# EasyEDA_schematics.net
KiCad netlist of a schematic drawn in EasyEDA
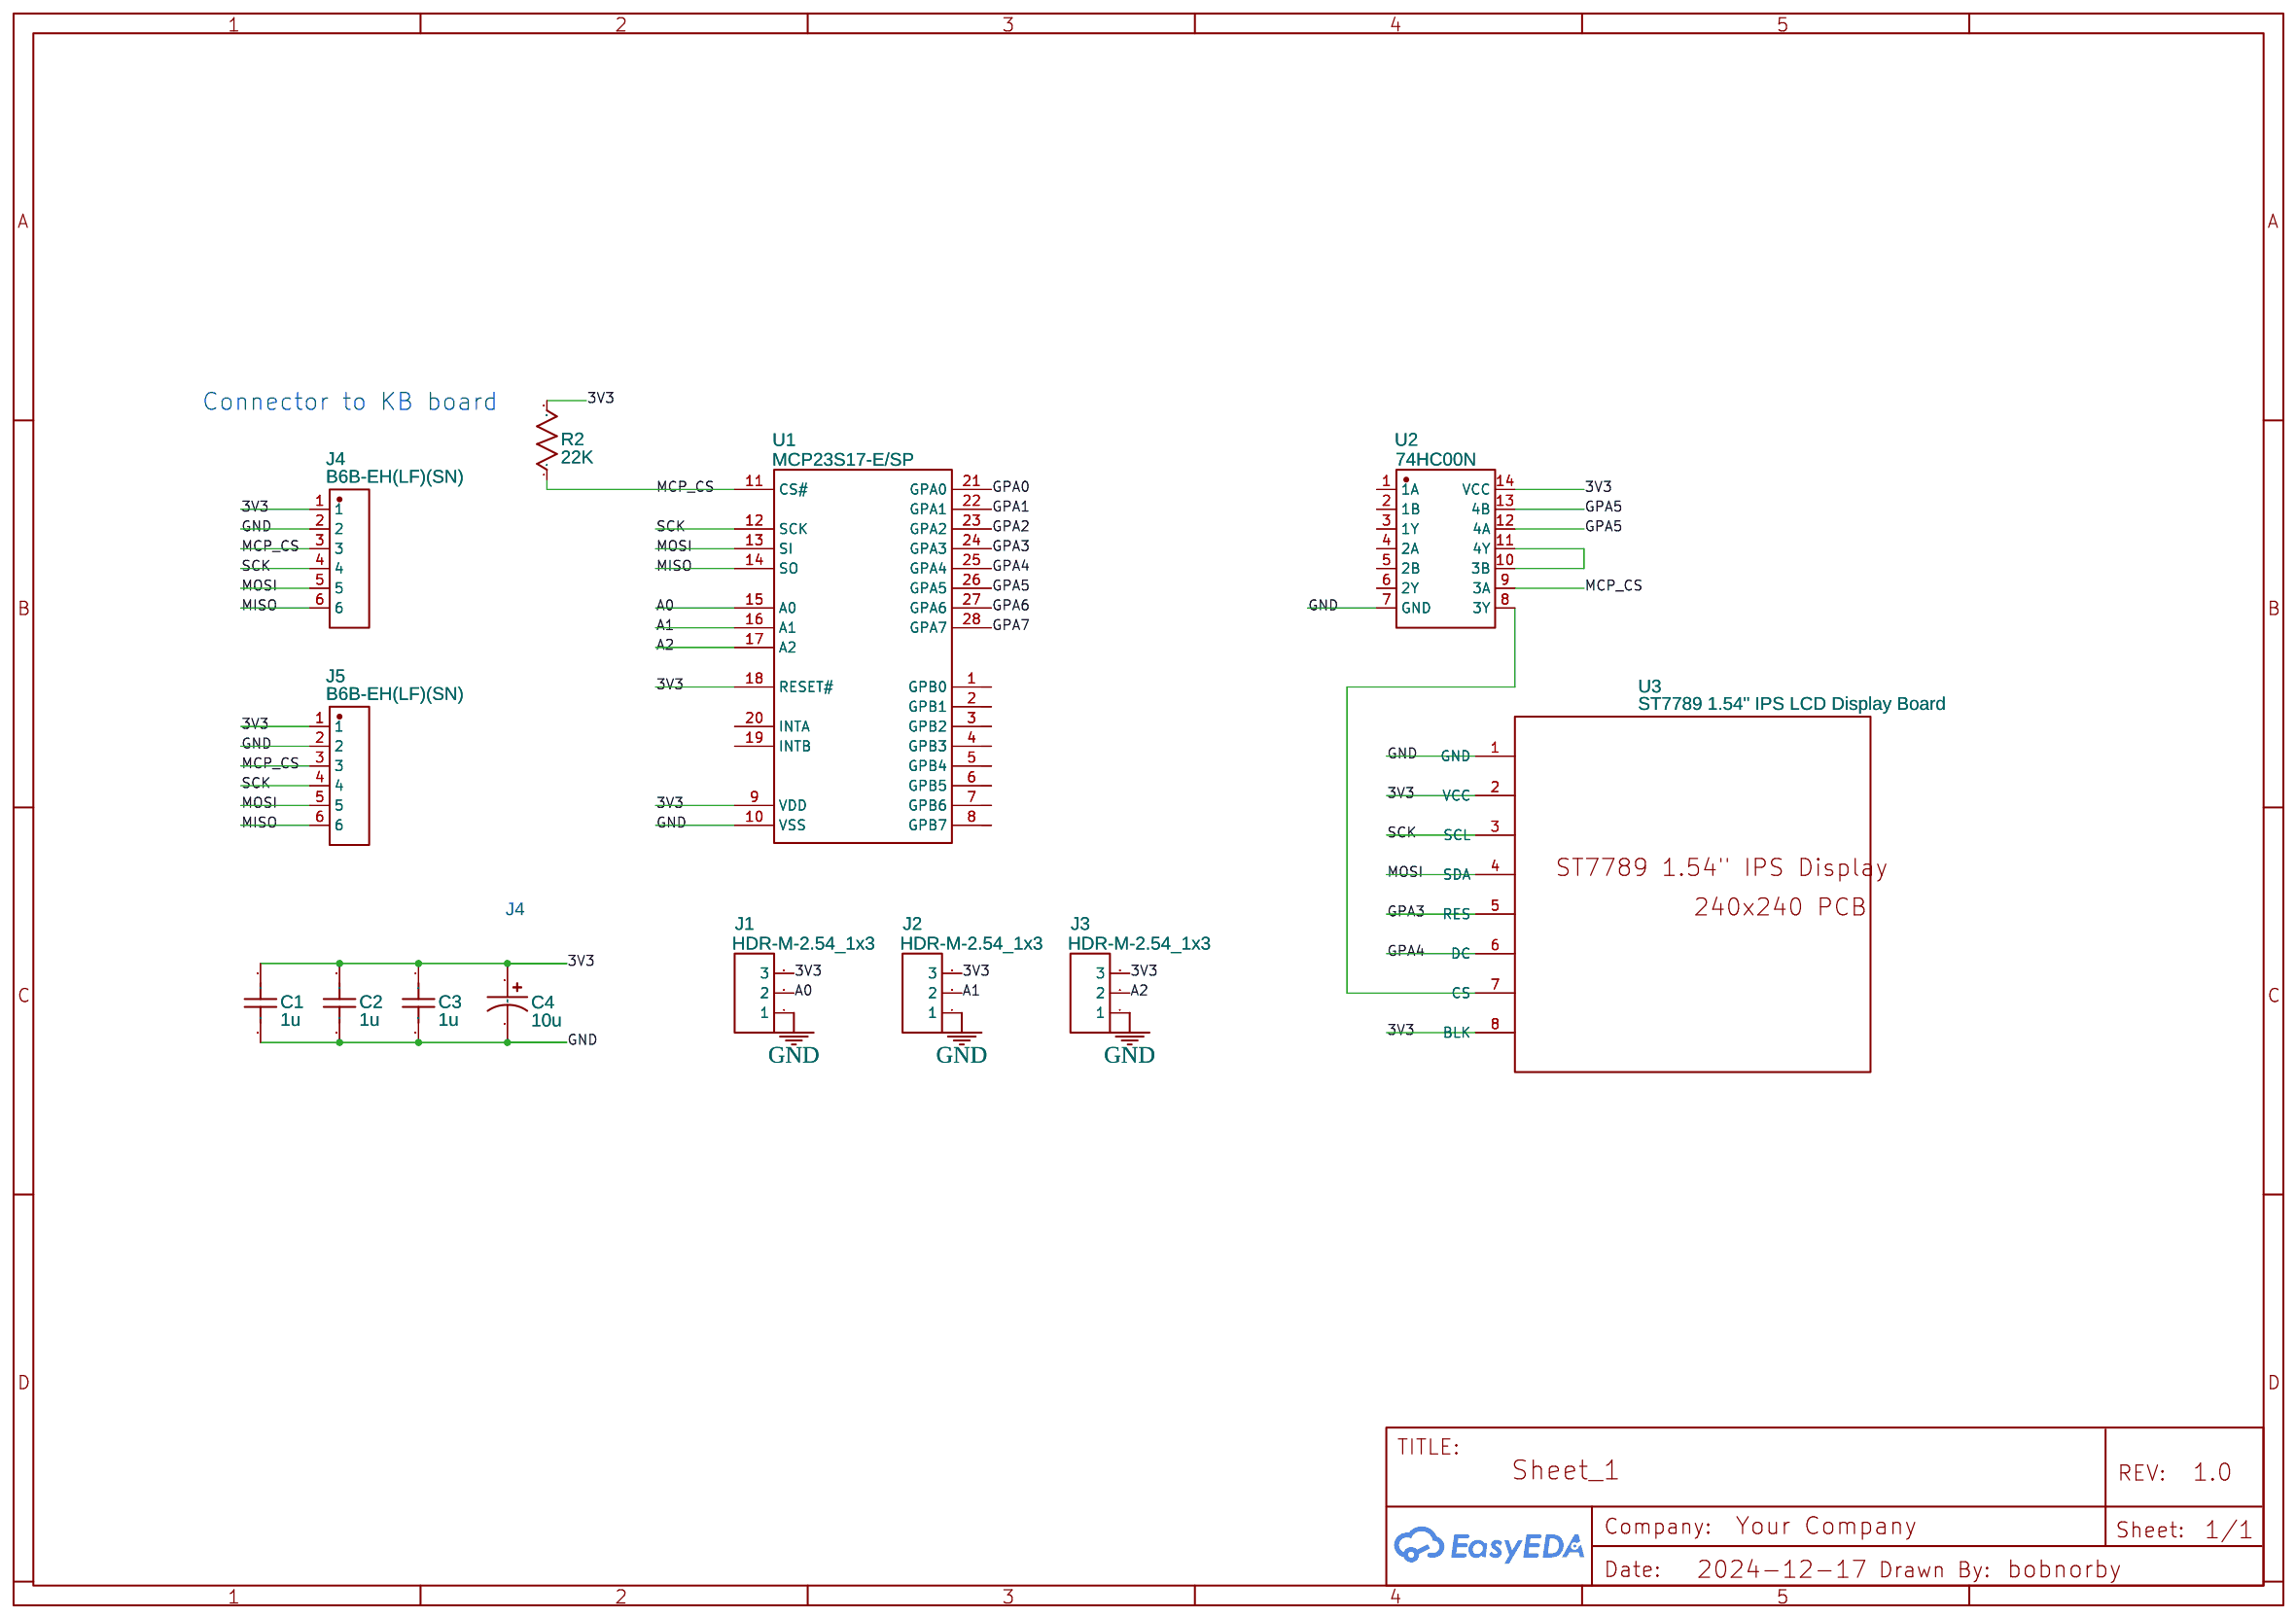
[diagram p0: schematic sheet]

(export (version "E")
  (design (tool "Eeschema 10.0.6"))
  (components
    (comp (ref "C1") (value "1u") (libsource (lib "") (part "C_RAD-0.1_US")))
    (comp (ref "C2") (value "1u") (libsource (lib "") (part "C_RAD-0.1_US")))
    (comp (ref "C3") (value "1u") (libsource (lib "") (part "C_RAD-0.1_US")))
    (comp (ref "C4") (value "10u") (libsource (lib "") (part "CE_TH_D5.0×F2.0_US")))
    (comp (ref "J1") (value "HDR-M-2.54_1x3") (libsource (lib "") (part "HDR-M-2.54_1x3")))
    (comp (ref "J2") (value "HDR-M-2.54_1x3") (libsource (lib "") (part "HDR-M-2.54_1x3")))
    (comp (ref "J3") (value "HDR-M-2.54_1x3") (libsource (lib "") (part "HDR-M-2.54_1x3")))
    (comp (ref "J4")
      (value "B6B-EH(LF)(SN)")
      (fields (field (name "Manufacturer") "JST"))
      (libsource (lib "") (part "B6B-EH(LF)(SN)"))
    )
    (comp (ref "J5")
      (value "B6B-EH(LF)(SN)")
      (fields (field (name "Manufacturer") "JST"))
      (libsource (lib "") (part "B6B-EH(LF)(SN)"))
    )
    (comp (ref "R2") (value "22K") (libsource (lib "") (part "R_AXIAL-0.3_US")))
    (comp (ref "U1")
      (value "MCP23S17-E/SP")
      (fields (field (name "Manufacturer") "MICROCHIP(美国微芯)"))
      (libsource (lib "") (part "MCP23S17-E/SP"))
    )
    (comp (ref "U2")
      (value "74HC00N")
      (fields (field (name "Manufacturer") "HGSEMI(华冠)"))
      (libsource (lib "") (part "74HC00N"))
    )
    (comp (ref "U3")
      (value "ST7789 1.54\" IPS LCD Display Board")
      (libsource (lib "") (part "ST7789 1.54{dblquote} IPS LCD Display Board"))
    )
  )
  (nets
    (net (code "1") (name "/3V3") (class "Default")
      (node (ref "C1") (pin "1") (pinfunction "1_1") (pintype "unspecified"))
      (node (ref "C2") (pin "1") (pinfunction "1_1") (pintype "unspecified"))
      (node (ref "C3") (pin "1") (pinfunction "1_1") (pintype "unspecified"))
      (node (ref "C4") (pin "1") (pinfunction "1_1") (pintype "unspecified"))
      (node (ref "J1") (pin "3") (pinfunction "3_3") (pintype "input"))
      (node (ref "J2") (pin "3") (pinfunction "3_3") (pintype "input"))
      (node (ref "J3") (pin "3") (pinfunction "3_3") (pintype "input"))
      (node (ref "J4") (pin "1") (pinfunction "1_1") (pintype "unspecified"))
      (node (ref "J5") (pin "1") (pinfunction "1_1") (pintype "unspecified"))
      (node (ref "R2") (pin "2") (pinfunction "2_2") (pintype "unspecified"))
      (node (ref "U1") (pin "18") (pinfunction "RESET#_18") (pintype "unspecified"))
      (node (ref "U1") (pin "9") (pinfunction "VDD_9") (pintype "passive"))
      (node (ref "U2") (pin "14") (pinfunction "VCC_14") (pintype "unspecified"))
      (node (ref "U3") (pin "2") (pinfunction "VCC_2") (pintype "unspecified"))
      (node (ref "U3") (pin "8") (pinfunction "BLK_8") (pintype "unspecified"))
    )
    (net (code "2") (name "/A0") (class "Default")
      (node (ref "J1") (pin "2") (pinfunction "2_2") (pintype "input"))
      (node (ref "U1") (pin "15") (pinfunction "A0_15") (pintype "unspecified"))
    )
    (net (code "3") (name "/A1") (class "Default")
      (node (ref "J2") (pin "2") (pinfunction "2_2") (pintype "input"))
      (node (ref "U1") (pin "16") (pinfunction "A1_16") (pintype "unspecified"))
    )
    (net (code "4") (name "/A2") (class "Default")
      (node (ref "J3") (pin "2") (pinfunction "2_2") (pintype "input"))
      (node (ref "U1") (pin "17") (pinfunction "A2_17") (pintype "unspecified"))
    )
    (net (code "5") (name "/GPA0") (class "Default")
      (node (ref "U1") (pin "21") (pinfunction "GPA0_21") (pintype "bidirectional"))
    )
    (net (code "6") (name "/GPA1") (class "Default")
      (node (ref "U1") (pin "22") (pinfunction "GPA1_22") (pintype "bidirectional"))
    )
    (net (code "7") (name "/GPA2") (class "Default")
      (node (ref "U1") (pin "23") (pinfunction "GPA2_23") (pintype "bidirectional"))
    )
    (net (code "8") (name "/GPA3") (class "Default")
      (node (ref "U1") (pin "24") (pinfunction "GPA3_24") (pintype "bidirectional"))
      (node (ref "U3") (pin "5") (pinfunction "RES_5") (pintype "unspecified"))
    )
    (net (code "9") (name "/GPA4") (class "Default")
      (node (ref "U1") (pin "25") (pinfunction "GPA4_25") (pintype "bidirectional"))
      (node (ref "U3") (pin "6") (pinfunction "DC_6") (pintype "unspecified"))
    )
    (net (code "10") (name "/GPA5") (class "Default")
      (node (ref "U1") (pin "26") (pinfunction "GPA5_26") (pintype "bidirectional"))
      (node (ref "U2") (pin "12") (pinfunction "4A_12") (pintype "unspecified"))
      (node (ref "U2") (pin "13") (pinfunction "4B_13") (pintype "unspecified"))
    )
    (net (code "11") (name "/GPA6") (class "Default")
      (node (ref "U1") (pin "27") (pinfunction "GPA6_27") (pintype "bidirectional"))
    )
    (net (code "12") (name "/GPA7") (class "Default")
      (node (ref "U1") (pin "28") (pinfunction "GPA7_28") (pintype "bidirectional"))
    )
    (net (code "13") (name "/MCP_CS") (class "Default")
      (node (ref "J4") (pin "3") (pinfunction "3_3") (pintype "unspecified"))
      (node (ref "J5") (pin "3") (pinfunction "3_3") (pintype "unspecified"))
      (node (ref "R2") (pin "1") (pinfunction "1_1") (pintype "unspecified"))
      (node (ref "U1") (pin "11") (pinfunction "CS#_11") (pintype "unspecified"))
      (node (ref "U2") (pin "9") (pinfunction "3A_9") (pintype "unspecified"))
    )
    (net (code "14") (name "/MISO") (class "Default")
      (node (ref "J4") (pin "6") (pinfunction "6_6") (pintype "unspecified"))
      (node (ref "J5") (pin "6") (pinfunction "6_6") (pintype "unspecified"))
      (node (ref "U1") (pin "14") (pinfunction "SO_14") (pintype "unspecified"))
    )
    (net (code "15") (name "/MOSI") (class "Default")
      (node (ref "J4") (pin "5") (pinfunction "5_5") (pintype "unspecified"))
      (node (ref "J5") (pin "5") (pinfunction "5_5") (pintype "unspecified"))
      (node (ref "U1") (pin "13") (pinfunction "SI_13") (pintype "unspecified"))
      (node (ref "U3") (pin "4") (pinfunction "SDA_4") (pintype "unspecified"))
    )
    (net (code "16") (name "/SCK") (class "Default")
      (node (ref "J4") (pin "4") (pinfunction "4_4") (pintype "unspecified"))
      (node (ref "J5") (pin "4") (pinfunction "4_4") (pintype "unspecified"))
      (node (ref "U1") (pin "12") (pinfunction "SCK_12") (pintype "unspecified"))
      (node (ref "U3") (pin "3") (pinfunction "SCL_3") (pintype "unspecified"))
    )
    (net (code "17") (name "GND") (class "Default")
      (node (ref "C1") (pin "2") (pinfunction "2_2") (pintype "unspecified"))
      (node (ref "C2") (pin "2") (pinfunction "2_2") (pintype "unspecified"))
      (node (ref "C3") (pin "2") (pinfunction "2_2") (pintype "unspecified"))
      (node (ref "C4") (pin "2") (pinfunction "2_2") (pintype "unspecified"))
      (node (ref "J1") (pin "1") (pinfunction "1_1") (pintype "input"))
      (node (ref "J2") (pin "1") (pinfunction "1_1") (pintype "input"))
      (node (ref "J3") (pin "1") (pinfunction "1_1") (pintype "input"))
      (node (ref "J4") (pin "2") (pinfunction "2_2") (pintype "unspecified"))
      (node (ref "J5") (pin "2") (pinfunction "2_2") (pintype "unspecified"))
      (node (ref "U1") (pin "10") (pinfunction "VSS_10") (pintype "passive"))
      (node (ref "U2") (pin "7") (pinfunction "GND_7") (pintype "unspecified"))
      (node (ref "U3") (pin "1") (pinfunction "GND_1") (pintype "unspecified"))
    )
    (net (code "18") (name "Net-(U2-3B)") (class "Default")
      (node (ref "U2") (pin "10") (pinfunction "3B_10") (pintype "unspecified"))
      (node (ref "U2") (pin "11") (pinfunction "4Y_11") (pintype "unspecified"))
    )
    (net (code "19") (name "Net-(U2-3Y)") (class "Default")
      (node (ref "U2") (pin "8") (pinfunction "3Y_8") (pintype "unspecified"))
      (node (ref "U3") (pin "7") (pinfunction "CS_7") (pintype "unspecified"))
    )
    (net (code "20") (name "unconnected-(U1-GPB0-Pad1)") (class "Default")
      (node (ref "U1") (pin "1") (pinfunction "GPB0_1") (pintype "bidirectional"))
    )
    (net (code "21") (name "unconnected-(U1-GPB1-Pad2)") (class "Default")
      (node (ref "U1") (pin "2") (pinfunction "GPB1_2") (pintype "bidirectional"))
    )
    (net (code "22") (name "unconnected-(U1-GPB2-Pad3)") (class "Default")
      (node (ref "U1") (pin "3") (pinfunction "GPB2_3") (pintype "bidirectional"))
    )
    (net (code "23") (name "unconnected-(U1-GPB3-Pad4)") (class "Default")
      (node (ref "U1") (pin "4") (pinfunction "GPB3_4") (pintype "bidirectional"))
    )
    (net (code "24") (name "unconnected-(U1-GPB4-Pad5)") (class "Default")
      (node (ref "U1") (pin "5") (pinfunction "GPB4_5") (pintype "bidirectional"))
    )
    (net (code "25") (name "unconnected-(U1-GPB5-Pad6)") (class "Default")
      (node (ref "U1") (pin "6") (pinfunction "GPB5_6") (pintype "bidirectional"))
    )
    (net (code "26") (name "unconnected-(U1-GPB6-Pad7)") (class "Default")
      (node (ref "U1") (pin "7") (pinfunction "GPB6_7") (pintype "bidirectional"))
    )
    (net (code "27") (name "unconnected-(U1-GPB7-Pad8)") (class "Default")
      (node (ref "U1") (pin "8") (pinfunction "GPB7_8") (pintype "bidirectional"))
    )
    (net (code "28") (name "unconnected-(U1-INTA-Pad20)") (class "Default")
      (node (ref "U1") (pin "20") (pinfunction "INTA_20") (pintype "unspecified"))
    )
    (net (code "29") (name "unconnected-(U1-INTB-Pad19)") (class "Default")
      (node (ref "U1") (pin "19") (pinfunction "INTB_19") (pintype "unspecified"))
    )
    (net (code "30") (name "unconnected-(U2-1A-Pad1)") (class "Default")
      (node (ref "U2") (pin "1") (pinfunction "1A_1") (pintype "unspecified"))
    )
    (net (code "31") (name "unconnected-(U2-1B-Pad2)") (class "Default")
      (node (ref "U2") (pin "2") (pinfunction "1B_2") (pintype "unspecified"))
    )
    (net (code "32") (name "unconnected-(U2-1Y-Pad3)") (class "Default")
      (node (ref "U2") (pin "3") (pinfunction "1Y_3") (pintype "unspecified"))
    )
    (net (code "33") (name "unconnected-(U2-2A-Pad4)") (class "Default")
      (node (ref "U2") (pin "4") (pinfunction "2A_4") (pintype "unspecified"))
    )
    (net (code "34") (name "unconnected-(U2-2B-Pad5)") (class "Default")
      (node (ref "U2") (pin "5") (pinfunction "2B_5") (pintype "unspecified"))
    )
    (net (code "35") (name "unconnected-(U2-2Y-Pad6)") (class "Default")
      (node (ref "U2") (pin "6") (pinfunction "2Y_6") (pintype "unspecified"))
    )
  )
)
